# Sheet1.net
KiCad netlist of a schematic drawn in Altium Designer
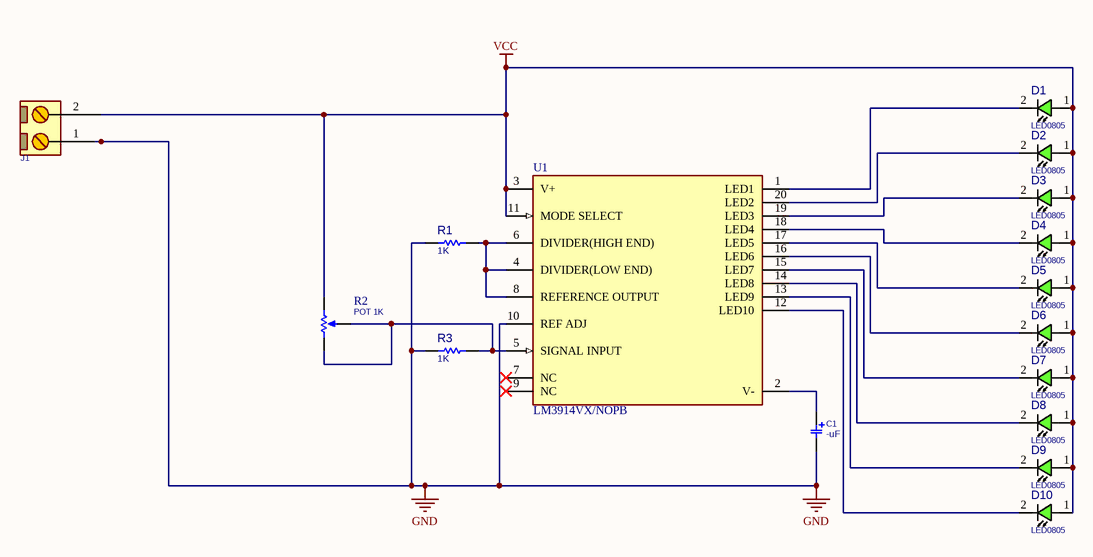
[diagram p0: Sheet1.SchDoc]

(export (version "E")
  (design (tool "Eeschema 10.0.6"))
  (components
    (comp (ref "C1")
      (value "-uF")
      (footprint "C_TN_3216")
      (description "CAP, SMD, TAN,")
      (libsource (lib "passive_smd") (part "CAP_SMD_TAN_3216"))
    )
    (comp (ref "D1")
      (value "LED0805")
      (footprint "LED0805")
      (description "LED, SMD, 0805")
      (fields (field (name "MANF") "MANF") (field (name "MANF_P#") "MANF_PART#"))
      (libsource (lib "led(diode)") (part "LED_SMD_0805"))
    )
    (comp (ref "D2")
      (value "LED0805")
      (footprint "LED0805")
      (description "LED, SMD, 0805")
      (fields (field (name "MANF") "MANF") (field (name "MANF_P#") "MANF_PART#"))
      (libsource (lib "led(diode)") (part "LED_SMD_0805"))
    )
    (comp (ref "D3")
      (value "LED0805")
      (footprint "LED0805")
      (description "LED, SMD, 0805")
      (fields (field (name "MANF") "MANF") (field (name "MANF_P#") "MANF_PART#"))
      (libsource (lib "led(diode)") (part "LED_SMD_0805"))
    )
    (comp (ref "D4")
      (value "LED0805")
      (footprint "LED0805")
      (description "LED, SMD, 0805")
      (fields (field (name "MANF") "MANF") (field (name "MANF_P#") "MANF_PART#"))
      (libsource (lib "led(diode)") (part "LED_SMD_0805"))
    )
    (comp (ref "D5")
      (value "LED0805")
      (footprint "LED0805")
      (description "LED, SMD, 0805")
      (fields (field (name "MANF") "MANF") (field (name "MANF_P#") "MANF_PART#"))
      (libsource (lib "led(diode)") (part "LED_SMD_0805"))
    )
    (comp (ref "D6")
      (value "LED0805")
      (footprint "LED0805")
      (description "LED, SMD, 0805")
      (fields (field (name "MANF") "MANF") (field (name "MANF_P#") "MANF_PART#"))
      (libsource (lib "led(diode)") (part "LED_SMD_0805"))
    )
    (comp (ref "D7")
      (value "LED0805")
      (footprint "LED0805")
      (description "LED, SMD, 0805")
      (fields (field (name "MANF") "MANF") (field (name "MANF_P#") "MANF_PART#"))
      (libsource (lib "led(diode)") (part "LED_SMD_0805"))
    )
    (comp (ref "D8")
      (value "LED0805")
      (footprint "LED0805")
      (description "LED, SMD, 0805")
      (fields (field (name "MANF") "MANF") (field (name "MANF_P#") "MANF_PART#"))
      (libsource (lib "led(diode)") (part "LED_SMD_0805"))
    )
    (comp (ref "D9")
      (value "LED0805")
      (footprint "LED0805")
      (description "LED, SMD, 0805")
      (fields (field (name "MANF") "MANF") (field (name "MANF_P#") "MANF_PART#"))
      (libsource (lib "led(diode)") (part "LED_SMD_0805"))
    )
    (comp (ref "D10")
      (value "LED0805")
      (footprint "LED0805")
      (description "LED, SMD, 0805")
      (fields (field (name "MANF") "MANF") (field (name "MANF_P#") "MANF_PART#"))
      (libsource (lib "led(diode)") (part "LED_SMD_0805"))
    )
    (comp (ref "J1")
      (value "CONN_TB2")
      (footprint "TBB_2")
      (description "CONN, TERMINAL BLOCK, 5.08mm pitch")
      (libsource (lib "conn_terminalB") (part "CONN_TB2"))
    )
    (comp (ref "R1")
      (value "1K")
      (footprint "R0805")
      (description "RESISTOR, SMD")
      (libsource (lib "passive_smd") (part "RES_SMD_0805"))
    )
    (comp (ref "R2")
      (value "POT 1K")
      (footprint "POTS_3314G")
      (description "RESISTOR, SMD, Potentiometer")
      (libsource (lib "resistor_pot_trimmer") (part "RES_SMD_POT_3314G"))
    )
    (comp (ref "R3")
      (value "1K")
      (footprint "R0805")
      (description "RESISTOR, SMD")
      (libsource (lib "passive_smd") (part "RES_SMD_0805"))
    )
    (comp (ref "U1")
      (value "LM3914VX/NOPB")
      (footprint "FP-FN0020A-IPC_B")
      (description "IC DRVR DOT/BAR DISPLAY 20PLCC")
      (fields
        (field (name "OCTOPART") "https://octopart.com/lm3914vx%2Fnopb-texas+instruments-24814204")
        (field (name "MANUFACTURER") "Texas Instruments")
      )
      (libsource (lib "LM3914VX_LED_Driver") (part "CMP-04914-000012-1"))
    )
  )
  (nets
    (net (code "1") (name "GND") (class "Default")
      (node (ref "C1") (pin "2") (pinfunction "2_2") (pintype "passive"))
      (node (ref "J1") (pin "1") (pinfunction "1_1") (pintype "passive"))
      (node (ref "R1") (pin "1") (pinfunction "1_1") (pintype "passive"))
      (node (ref "R3") (pin "1") (pinfunction "1_1") (pintype "passive"))
      (node (ref "U1") (pin "10") (pinfunction "REF_ADJ_10") (pintype "passive"))
    )
    (net (code "2") (name "Net-(D1-CATHODE)") (class "Default")
      (node (ref "D1") (pin "2") (pinfunction "CATHODE_2") (pintype "passive"))
      (node (ref "U1") (pin "1") (pinfunction "LED1_1") (pintype "open_collector"))
    )
    (net (code "3") (name "Net-(D2-CATHODE)") (class "Default")
      (node (ref "D2") (pin "2") (pinfunction "CATHODE_2") (pintype "passive"))
      (node (ref "U1") (pin "20") (pinfunction "LED2_20") (pintype "open_collector"))
    )
    (net (code "4") (name "Net-(D3-CATHODE)") (class "Default")
      (node (ref "D3") (pin "2") (pinfunction "CATHODE_2") (pintype "passive"))
      (node (ref "U1") (pin "19") (pinfunction "LED3_19") (pintype "open_collector"))
    )
    (net (code "5") (name "Net-(D4-CATHODE)") (class "Default")
      (node (ref "D4") (pin "2") (pinfunction "CATHODE_2") (pintype "passive"))
      (node (ref "U1") (pin "18") (pinfunction "LED4_18") (pintype "open_collector"))
    )
    (net (code "6") (name "Net-(D5-CATHODE)") (class "Default")
      (node (ref "D5") (pin "2") (pinfunction "CATHODE_2") (pintype "passive"))
      (node (ref "U1") (pin "17") (pinfunction "LED5_17") (pintype "open_collector"))
    )
    (net (code "7") (name "Net-(D6-CATHODE)") (class "Default")
      (node (ref "D6") (pin "2") (pinfunction "CATHODE_2") (pintype "passive"))
      (node (ref "U1") (pin "16") (pinfunction "LED6_16") (pintype "open_collector"))
    )
    (net (code "8") (name "Net-(D7-CATHODE)") (class "Default")
      (node (ref "D7") (pin "2") (pinfunction "CATHODE_2") (pintype "passive"))
      (node (ref "U1") (pin "15") (pinfunction "LED7_15") (pintype "open_collector"))
    )
    (net (code "9") (name "Net-(D8-CATHODE)") (class "Default")
      (node (ref "D8") (pin "2") (pinfunction "CATHODE_2") (pintype "passive"))
      (node (ref "U1") (pin "14") (pinfunction "LED8_14") (pintype "open_collector"))
    )
    (net (code "10") (name "Net-(D9-CATHODE)") (class "Default")
      (node (ref "D9") (pin "2") (pinfunction "CATHODE_2") (pintype "passive"))
      (node (ref "U1") (pin "13") (pinfunction "LED9_13") (pintype "open_collector"))
    )
    (net (code "11") (name "Net-(D10-CATHODE)") (class "Default")
      (node (ref "D10") (pin "2") (pinfunction "CATHODE_2") (pintype "passive"))
      (node (ref "U1") (pin "12") (pinfunction "LED10_12") (pintype "open_collector"))
    )
    (net (code "12") (name "Net-(R2-TAP)") (class "Default")
      (node (ref "R2") (pin "1") (pinfunction "TOP_1") (pintype "passive"))
      (node (ref "R2") (pin "2") (pinfunction "TAP_2") (pintype "passive"))
      (node (ref "R3") (pin "2") (pinfunction "2_2") (pintype "passive"))
      (node (ref "U1") (pin "5") (pinfunction "SIGNAL_INPUT_5") (pintype "input"))
    )
    (net (code "13") (name "Net-(U1-DIVIDER(HIGH_END))") (class "Default")
      (node (ref "R1") (pin "2") (pinfunction "2_2") (pintype "passive"))
      (node (ref "U1") (pin "4") (pinfunction "DIVIDER(LOW_END)_4") (pintype "passive"))
      (node (ref "U1") (pin "6") (pinfunction "DIVIDER(HIGH_END)_6") (pintype "passive"))
      (node (ref "U1") (pin "8") (pinfunction "REFERENCE_OUTPUT_8") (pintype "passive"))
    )
    (net (code "14") (name "Net-(U1-V-)") (class "Default")
      (node (ref "C1") (pin "1") (pinfunction "1_1") (pintype "passive"))
      (node (ref "U1") (pin "2") (pinfunction "V-_2") (pintype "power_in"))
    )
    (net (code "15") (name "VCC") (class "Default")
      (node (ref "D1") (pin "1") (pinfunction "ANODE_1") (pintype "passive"))
      (node (ref "D10") (pin "1") (pinfunction "ANODE_1") (pintype "passive"))
      (node (ref "D2") (pin "1") (pinfunction "ANODE_1") (pintype "passive"))
      (node (ref "D3") (pin "1") (pinfunction "ANODE_1") (pintype "passive"))
      (node (ref "D4") (pin "1") (pinfunction "ANODE_1") (pintype "passive"))
      (node (ref "D5") (pin "1") (pinfunction "ANODE_1") (pintype "passive"))
      (node (ref "D6") (pin "1") (pinfunction "ANODE_1") (pintype "passive"))
      (node (ref "D7") (pin "1") (pinfunction "ANODE_1") (pintype "passive"))
      (node (ref "D8") (pin "1") (pinfunction "ANODE_1") (pintype "passive"))
      (node (ref "D9") (pin "1") (pinfunction "ANODE_1") (pintype "passive"))
      (node (ref "J1") (pin "2") (pinfunction "2_2") (pintype "passive"))
      (node (ref "R2") (pin "3") (pinfunction "BOT_3") (pintype "passive"))
      (node (ref "U1") (pin "11") (pinfunction "MODE_SELECT_11") (pintype "input"))
      (node (ref "U1") (pin "3") (pinfunction "V+_3") (pintype "power_in"))
    )
    (net (code "16") (name "unconnected-(U1-NC-Pad7)") (class "Default")
      (node (ref "U1") (pin "7") (pinfunction "NC_7") (pintype "passive+no_connect"))
    )
    (net (code "17") (name "unconnected-(U1-NC-Pad9)") (class "Default")
      (node (ref "U1") (pin "9") (pinfunction "NC_9") (pintype "passive+no_connect"))
    )
  )
)
